# Arduino_CS.net
KiCad netlist of a schematic drawn in EAGLE
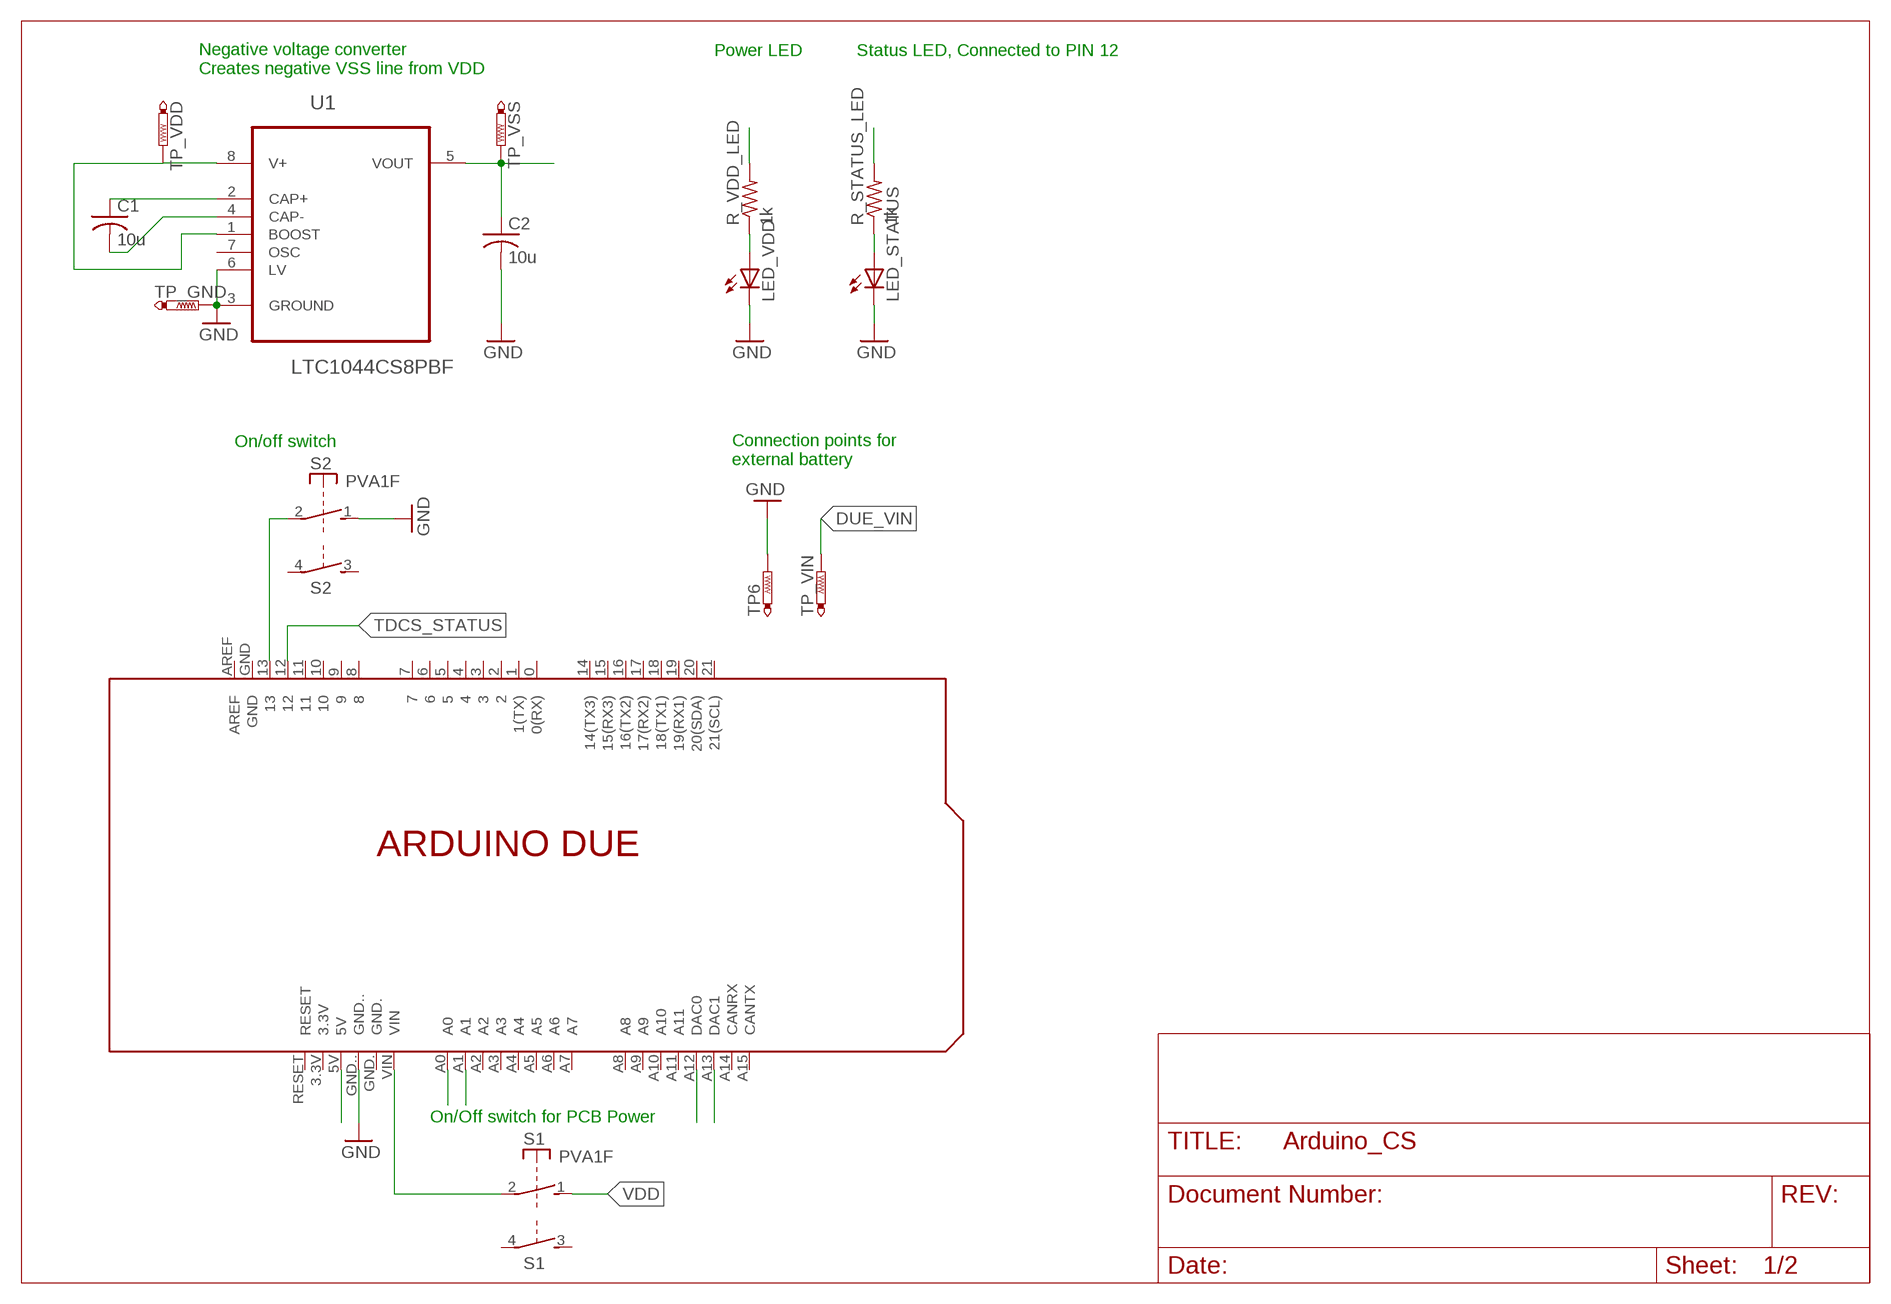
[diagram p0: schematic, sheet 1]
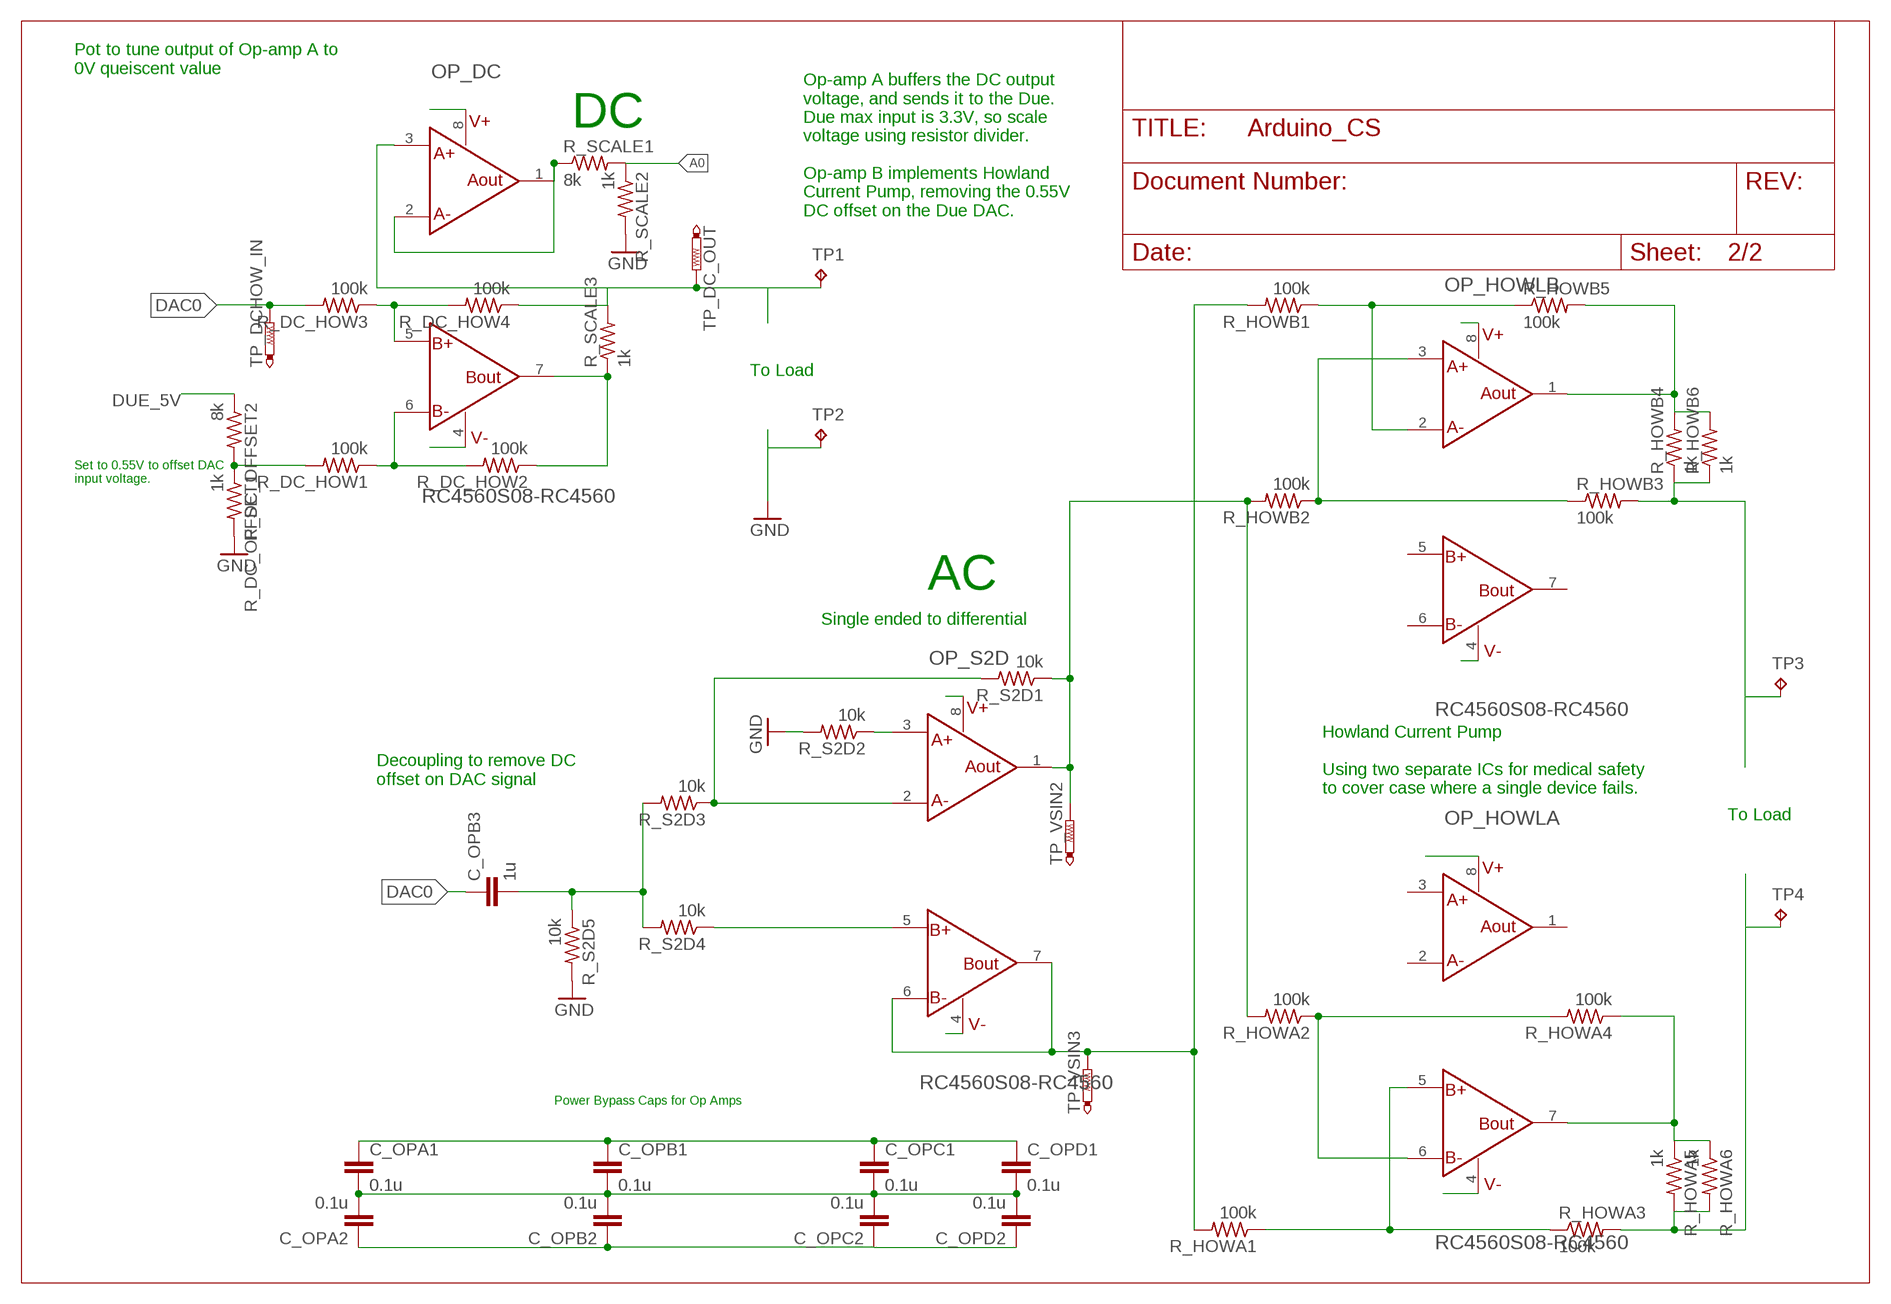
[diagram p1: schematic, sheet 2]

(export (version "E")
  (design (tool "Eeschema 10.0.6"))
  (components
    (comp (ref "C_OPA1")
      (value "0.1u")
      (footprint "eagle-import:C0805")
      (libsource (lib "eagle-import") (part "C-EUC0805"))
    )
    (comp (ref "C_OPA2")
      (value "0.1u")
      (footprint "eagle-import:C0805")
      (libsource (lib "eagle-import") (part "C-EUC0805"))
    )
    (comp (ref "C_OPB1")
      (value "0.1u")
      (footprint "eagle-import:C0805")
      (libsource (lib "eagle-import") (part "C-EUC0805"))
    )
    (comp (ref "C_OPB2")
      (value "0.1u")
      (footprint "eagle-import:C0805")
      (libsource (lib "eagle-import") (part "C-EUC0805"))
    )
    (comp (ref "C_OPB3")
      (value "1u")
      (footprint "eagle-import:C0805")
      (libsource (lib "eagle-import") (part "C-EUC0805"))
    )
    (comp (ref "C_OPC1")
      (value "0.1u")
      (footprint "eagle-import:C0805")
      (libsource (lib "eagle-import") (part "C-EUC0805"))
    )
    (comp (ref "C_OPC2")
      (value "0.1u")
      (footprint "eagle-import:C0805")
      (libsource (lib "eagle-import") (part "C-EUC0805"))
    )
    (comp (ref "C_OPD1")
      (value "0.1u")
      (footprint "eagle-import:C0805")
      (libsource (lib "eagle-import") (part "C-EUC0805"))
    )
    (comp (ref "C_OPD2")
      (value "0.1u")
      (footprint "eagle-import:C0805")
      (libsource (lib "eagle-import") (part "C-EUC0805"))
    )
    (comp (ref "OP_DC")
      (value "RC4560S08-RC4560")
      (footprint "eagle-import:SO8")
      (libsource (lib "eagle-import") (part "RC4560S08-RC4560"))
    )
    (comp (ref "OP_HOWLA")
      (value "RC4560S08-RC4560")
      (footprint "eagle-import:SO8")
      (libsource (lib "eagle-import") (part "RC4560S08-RC4560"))
    )
    (comp (ref "OP_HOWLB")
      (value "RC4560S08-RC4560")
      (footprint "eagle-import:SO8")
      (libsource (lib "eagle-import") (part "RC4560S08-RC4560"))
    )
    (comp (ref "OP_S2D")
      (value "RC4560S08-RC4560")
      (footprint "eagle-import:SO8")
      (libsource (lib "eagle-import") (part "RC4560S08-RC4560"))
    )
    (comp (ref "R_DC_HOW1")
      (value "100k")
      (footprint "eagle-import:R0805")
      (libsource (lib "eagle-import") (part "R-US_R0805"))
    )
    (comp (ref "R_DC_HOW2")
      (value "100k")
      (footprint "eagle-import:R0805")
      (libsource (lib "eagle-import") (part "R-US_R0805"))
    )
    (comp (ref "R_DC_HOW3")
      (value "100k")
      (footprint "eagle-import:R0805")
      (libsource (lib "eagle-import") (part "R-US_R0805"))
    )
    (comp (ref "R_DC_HOW4")
      (value "100k")
      (footprint "eagle-import:R0805")
      (libsource (lib "eagle-import") (part "R-US_R0805"))
    )
    (comp (ref "R_DC_OFFSET1")
      (value "1k")
      (footprint "eagle-import:R0805")
      (libsource (lib "eagle-import") (part "R-US_R0805"))
    )
    (comp (ref "R_DC_OFFSET2")
      (value "8k")
      (footprint "eagle-import:R0805")
      (libsource (lib "eagle-import") (part "R-US_R0805"))
    )
    (comp (ref "R_HOWA1")
      (value "100k")
      (footprint "eagle-import:R0805")
      (libsource (lib "eagle-import") (part "R-US_R0805"))
    )
    (comp (ref "R_HOWA2")
      (value "100k")
      (footprint "eagle-import:R0805")
      (libsource (lib "eagle-import") (part "R-US_R0805"))
    )
    (comp (ref "R_HOWA3")
      (value "100k")
      (footprint "eagle-import:R0805")
      (libsource (lib "eagle-import") (part "R-US_R0805"))
    )
    (comp (ref "R_HOWA4")
      (value "100k")
      (footprint "eagle-import:R0805")
      (libsource (lib "eagle-import") (part "R-US_R0805"))
    )
    (comp (ref "R_HOWA5")
      (value "1k")
      (footprint "eagle-import:R0805")
      (libsource (lib "eagle-import") (part "R-US_R0805"))
    )
    (comp (ref "R_HOWA6")
      (value "1k")
      (footprint "eagle-import:R0805")
      (libsource (lib "eagle-import") (part "R-US_R0805"))
    )
    (comp (ref "R_HOWB1")
      (value "100k")
      (footprint "eagle-import:R0805")
      (libsource (lib "eagle-import") (part "R-US_R0805"))
    )
    (comp (ref "R_HOWB2")
      (value "100k")
      (footprint "eagle-import:R0805")
      (libsource (lib "eagle-import") (part "R-US_R0805"))
    )
    (comp (ref "R_HOWB3")
      (value "100k")
      (footprint "eagle-import:R0805")
      (libsource (lib "eagle-import") (part "R-US_R0805"))
    )
    (comp (ref "R_HOWB4")
      (value "1k")
      (footprint "eagle-import:R0805")
      (libsource (lib "eagle-import") (part "R-US_R0805"))
    )
    (comp (ref "R_HOWB5")
      (value "100k")
      (footprint "eagle-import:R0805")
      (libsource (lib "eagle-import") (part "R-US_R0805"))
    )
    (comp (ref "R_HOWB6")
      (value "1k")
      (footprint "eagle-import:R0805")
      (libsource (lib "eagle-import") (part "R-US_R0805"))
    )
    (comp (ref "R_S2D1")
      (value "10k")
      (footprint "eagle-import:R0805")
      (libsource (lib "eagle-import") (part "R-US_R0805"))
    )
    (comp (ref "R_S2D2")
      (value "10k")
      (footprint "eagle-import:R0805")
      (libsource (lib "eagle-import") (part "R-US_R0805"))
    )
    (comp (ref "R_S2D3")
      (value "10k")
      (footprint "eagle-import:R0805")
      (libsource (lib "eagle-import") (part "R-US_R0805"))
    )
    (comp (ref "R_S2D4")
      (value "10k")
      (footprint "eagle-import:R0805")
      (libsource (lib "eagle-import") (part "R-US_R0805"))
    )
    (comp (ref "R_S2D5")
      (value "10k")
      (footprint "eagle-import:R0805")
      (libsource (lib "eagle-import") (part "R-US_R0805"))
    )
    (comp (ref "R_SCALE1")
      (value "8k")
      (footprint "eagle-import:R0805")
      (libsource (lib "eagle-import") (part "R-US_R0805"))
    )
    (comp (ref "R_SCALE2")
      (value "1k")
      (footprint "eagle-import:R0805")
      (libsource (lib "eagle-import") (part "R-US_R0805"))
    )
    (comp (ref "R_SCALE3")
      (value "1k")
      (footprint "eagle-import:R0805")
      (libsource (lib "eagle-import") (part "R-US_R0805"))
    )
    (comp (ref "TP1")
      (value "TPPAD1-20")
      (footprint "eagle-import:P1-20")
      (libsource (lib "eagle-import") (part "TPPAD1-20"))
    )
    (comp (ref "TP2")
      (value "TPPAD1-20")
      (footprint "eagle-import:P1-20")
      (libsource (lib "eagle-import") (part "TPPAD1-20"))
    )
    (comp (ref "TP3")
      (value "TPPAD1-20")
      (footprint "eagle-import:P1-20")
      (libsource (lib "eagle-import") (part "TPPAD1-20"))
    )
    (comp (ref "TP4")
      (value "TPPAD1-20")
      (footprint "eagle-import:P1-20")
      (libsource (lib "eagle-import") (part "TPPAD1-20"))
    )
    (comp (ref "TP_DCHOW_IN")
      (value "PTR1PAD1-13")
      (footprint "eagle-import:P1-13")
      (libsource (lib "eagle-import") (part "PTR1PAD1-13"))
    )
    (comp (ref "TP_DC_OUT")
      (value "PTR1PAD1-13")
      (footprint "eagle-import:P1-13")
      (libsource (lib "eagle-import") (part "PTR1PAD1-13"))
    )
    (comp (ref "TP_VSIN2")
      (value "PTR1PAD1-13")
      (footprint "eagle-import:P1-13")
      (libsource (lib "eagle-import") (part "PTR1PAD1-13"))
    )
    (comp (ref "TP_VSIN3")
      (value "PTR1PAD1-13")
      (footprint "eagle-import:P1-13")
      (libsource (lib "eagle-import") (part "PTR1PAD1-13"))
    )
    (comp (ref "C1")
      (value "10u")
      (footprint "eagle-import:C0805")
      (libsource (lib "eagle-import") (part "C-USC0805"))
    )
    (comp (ref "C2")
      (value "10u")
      (footprint "eagle-import:C0805")
      (libsource (lib "eagle-import") (part "C-USC0805"))
    )
    (comp (ref "LED_STATUS")
      (value "LEDSML0805")
      (footprint "eagle-import:SML0805")
      (libsource (lib "eagle-import") (part "LEDSML0805"))
    )
    (comp (ref "LED_VDD")
      (value "LEDSML0805")
      (footprint "eagle-import:SML0805")
      (libsource (lib "eagle-import") (part "LEDSML0805"))
    )
    (comp (ref "PCB1")
      (value "ARDUINO_DUE")
      (footprint "eagle-import:ARDUINO_DUE")
      (libsource (lib "eagle-import") (part "ARDUINO_DUE"))
    )
    (comp (ref "R_STATUS_LED")
      (value "1k")
      (footprint "eagle-import:M0805")
      (libsource (lib "eagle-import") (part "resistor_R-US_M0805"))
    )
    (comp (ref "R_VDD_LED")
      (value "1k")
      (footprint "eagle-import:M0805")
      (libsource (lib "eagle-import") (part "resistor_R-US_M0805"))
    )
    (comp (ref "S1")
      (value "PVA1F")
      (footprint "eagle-import:PVA1F")
      (libsource (lib "eagle-import") (part "PVA1F"))
    )
    (comp (ref "S2")
      (value "PVA1F")
      (footprint "eagle-import:PVA1F")
      (libsource (lib "eagle-import") (part "PVA1F"))
    )
    (comp (ref "TP6")
      (value "PTR1PAD1-13")
      (footprint "eagle-import:P1-13")
      (libsource (lib "eagle-import") (part "PTR1PAD1-13"))
    )
    (comp (ref "TP_GND")
      (value "PTR1PAD1-13")
      (footprint "eagle-import:P1-13")
      (libsource (lib "eagle-import") (part "PTR1PAD1-13"))
    )
    (comp (ref "TP_VDD")
      (value "PTR1PAD1-13")
      (footprint "eagle-import:P1-13")
      (libsource (lib "eagle-import") (part "PTR1PAD1-13"))
    )
    (comp (ref "TP_VIN")
      (value "PTR1PAD1-13")
      (footprint "eagle-import:P1-13")
      (libsource (lib "eagle-import") (part "PTR1PAD1-13"))
    )
    (comp (ref "TP_VSS")
      (value "PTR1PAD1-13")
      (footprint "eagle-import:P1-13")
      (libsource (lib "eagle-import") (part "PTR1PAD1-13"))
    )
    (comp (ref "U1")
      (value "LTC1044CS8PBF")
      (footprint "eagle-import:SOIC127P600X175-8N")
      (fields (field (name "MPN") "LTC1044CS8#PBF"))
      (libsource (lib "eagle-import") (part "LTC1044CS8PBF"))
    )
  )
  (nets
    (net (code "1") (name "A0") (class "Default")
      (node (ref "PCB1") (pin "A0") (pinfunction "A0_A0") (pintype "bidirectional"))
      (node (ref "R_SCALE1") (pin "2") (pinfunction "2_2") (pintype "passive"))
      (node (ref "R_SCALE2") (pin "1") (pinfunction "1_1") (pintype "passive"))
    )
    (net (code "2") (name "DAC0") (class "Default")
      (node (ref "C_OPB3") (pin "1") (pinfunction "1_1") (pintype "passive"))
      (node (ref "PCB1") (pin "A12") (pinfunction "DAC0_A12") (pintype "bidirectional"))
      (node (ref "R_DC_HOW3") (pin "2") (pinfunction "2_2") (pintype "passive"))
      (node (ref "TP_DCHOW_IN") (pin "TP") (pinfunction "TP_TP") (pintype "input"))
    )
    (net (code "3") (name "DUE_5V") (class "Default")
      (node (ref "PCB1") (pin "5V") (pinfunction "5V_5V") (pintype "bidirectional"))
      (node (ref "R_DC_OFFSET2") (pin "1") (pinfunction "1_1") (pintype "passive"))
    )
    (net (code "4") (name "DUE_VIN") (class "Default")
      (node (ref "PCB1") (pin "VIN") (pinfunction "VIN_VIN") (pintype "bidirectional"))
      (node (ref "S1") (pin "2") (pinfunction "P_2") (pintype "passive"))
      (node (ref "TP_VIN") (pin "TP") (pinfunction "TP_TP") (pintype "input"))
    )
    (net (code "5") (name "GND") (class "Default")
      (node (ref "C2") (pin "2") (pinfunction "2_2") (pintype "passive"))
      (node (ref "C_OPA1") (pin "2") (pinfunction "2_2") (pintype "passive"))
      (node (ref "C_OPA2") (pin "2") (pinfunction "2_2") (pintype "passive"))
      (node (ref "C_OPB1") (pin "2") (pinfunction "2_2") (pintype "passive"))
      (node (ref "C_OPB2") (pin "2") (pinfunction "2_2") (pintype "passive"))
      (node (ref "C_OPC1") (pin "2") (pinfunction "2_2") (pintype "passive"))
      (node (ref "C_OPC2") (pin "2") (pinfunction "2_2") (pintype "passive"))
      (node (ref "C_OPD1") (pin "2") (pinfunction "2_2") (pintype "passive"))
      (node (ref "C_OPD2") (pin "2") (pinfunction "2_2") (pintype "passive"))
      (node (ref "LED_STATUS") (pin "C") (pinfunction "C_C") (pintype "passive"))
      (node (ref "LED_VDD") (pin "C") (pinfunction "C_C") (pintype "passive"))
      (node (ref "PCB1") (pin "GND..") (pinfunction "GND.._GND..") (pintype "bidirectional"))
      (node (ref "R_DC_OFFSET1") (pin "2") (pinfunction "2_2") (pintype "passive"))
      (node (ref "R_S2D2") (pin "2") (pinfunction "2_2") (pintype "passive"))
      (node (ref "R_S2D5") (pin "2") (pinfunction "2_2") (pintype "passive"))
      (node (ref "R_SCALE2") (pin "2") (pinfunction "2_2") (pintype "passive"))
      (node (ref "S2") (pin "1") (pinfunction "S_1") (pintype "passive"))
      (node (ref "TP2") (pin "TP") (pinfunction "TP_TP") (pintype "input"))
      (node (ref "TP6") (pin "TP") (pinfunction "TP_TP") (pintype "input"))
      (node (ref "TP_GND") (pin "TP") (pinfunction "TP_TP") (pintype "input"))
      (node (ref "U1") (pin "3") (pinfunction "GROUND_3") (pintype "passive"))
      (node (ref "U1") (pin "6") (pinfunction "LV_6") (pintype "input"))
    )
    (net (code "6") (name "Net-(C_OPB3-Pad2)") (class "Default")
      (node (ref "C_OPB3") (pin "2") (pinfunction "2_2") (pintype "passive"))
      (node (ref "R_S2D3") (pin "2") (pinfunction "2_2") (pintype "passive"))
      (node (ref "R_S2D4") (pin "2") (pinfunction "2_2") (pintype "passive"))
      (node (ref "R_S2D5") (pin "1") (pinfunction "1_1") (pintype "passive"))
    )
    (net (code "7") (name "Net-(LED_STATUS-PadA)") (class "Default")
      (node (ref "LED_STATUS") (pin "A") (pinfunction "A_A") (pintype "passive"))
      (node (ref "R_STATUS_LED") (pin "1") (pinfunction "1_1") (pintype "passive"))
    )
    (net (code "8") (name "Net-(LED_VDD-PadA)") (class "Default")
      (node (ref "LED_VDD") (pin "A") (pinfunction "A_A") (pintype "passive"))
      (node (ref "R_VDD_LED") (pin "1") (pinfunction "1_1") (pintype "passive"))
    )
    (net (code "9") (name "Net-(OP_DC-NEGA)") (class "Default")
      (node (ref "OP_DC") (pin "1") (pinfunction "OUTA_1") (pintype "output"))
      (node (ref "OP_DC") (pin "2") (pinfunction "NEGA_2") (pintype "input"))
      (node (ref "R_SCALE1") (pin "1") (pinfunction "1_1") (pintype "passive"))
    )
    (net (code "10") (name "Net-(OP_DC-NEGB)") (class "Default")
      (node (ref "OP_DC") (pin "6") (pinfunction "NEGB_6") (pintype "input"))
      (node (ref "R_DC_HOW1") (pin "1") (pinfunction "1_1") (pintype "passive"))
      (node (ref "R_DC_HOW2") (pin "2") (pinfunction "2_2") (pintype "passive"))
    )
    (net (code "11") (name "Net-(OP_DC-OUTB)") (class "Default")
      (node (ref "OP_DC") (pin "7") (pinfunction "OUTB_7") (pintype "output"))
      (node (ref "R_DC_HOW2") (pin "1") (pinfunction "1_1") (pintype "passive"))
      (node (ref "R_SCALE3") (pin "1") (pinfunction "1_1") (pintype "passive"))
    )
    (net (code "12") (name "Net-(OP_DC-POSA)") (class "Default")
      (node (ref "OP_DC") (pin "3") (pinfunction "POSA_3") (pintype "input"))
      (node (ref "R_DC_HOW4") (pin "1") (pinfunction "1_1") (pintype "passive"))
      (node (ref "R_SCALE3") (pin "2") (pinfunction "2_2") (pintype "passive"))
      (node (ref "TP1") (pin "TP") (pinfunction "TP_TP") (pintype "input"))
      (node (ref "TP_DC_OUT") (pin "TP") (pinfunction "TP_TP") (pintype "input"))
    )
    (net (code "13") (name "Net-(OP_DC-POSB)") (class "Default")
      (node (ref "OP_DC") (pin "5") (pinfunction "POSB_5") (pintype "input"))
      (node (ref "R_DC_HOW3") (pin "1") (pinfunction "1_1") (pintype "passive"))
      (node (ref "R_DC_HOW4") (pin "2") (pinfunction "2_2") (pintype "passive"))
    )
    (net (code "14") (name "Net-(OP_HOWLA-NEGB)") (class "Default")
      (node (ref "OP_HOWLA") (pin "6") (pinfunction "NEGB_6") (pintype "input"))
      (node (ref "R_HOWA2") (pin "1") (pinfunction "1_1") (pintype "passive"))
      (node (ref "R_HOWA4") (pin "2") (pinfunction "2_2") (pintype "passive"))
    )
    (net (code "15") (name "Net-(OP_HOWLA-OUTB)") (class "Default")
      (node (ref "OP_HOWLA") (pin "7") (pinfunction "OUTB_7") (pintype "output"))
      (node (ref "R_HOWA4") (pin "1") (pinfunction "1_1") (pintype "passive"))
      (node (ref "R_HOWA5") (pin "1") (pinfunction "1_1") (pintype "passive"))
      (node (ref "R_HOWA6") (pin "1") (pinfunction "1_1") (pintype "passive"))
    )
    (net (code "16") (name "Net-(OP_HOWLA-POSB)") (class "Default")
      (node (ref "OP_HOWLA") (pin "5") (pinfunction "POSB_5") (pintype "input"))
      (node (ref "R_HOWA1") (pin "1") (pinfunction "1_1") (pintype "passive"))
      (node (ref "R_HOWA3") (pin "1") (pinfunction "1_1") (pintype "passive"))
    )
    (net (code "17") (name "Net-(OP_HOWLB-NEGA)") (class "Default")
      (node (ref "OP_HOWLB") (pin "2") (pinfunction "NEGA_2") (pintype "input"))
      (node (ref "R_HOWB1") (pin "1") (pinfunction "1_1") (pintype "passive"))
      (node (ref "R_HOWB5") (pin "1") (pinfunction "1_1") (pintype "passive"))
    )
    (net (code "18") (name "Net-(OP_HOWLB-OUTA)") (class "Default")
      (node (ref "OP_HOWLB") (pin "1") (pinfunction "OUTA_1") (pintype "output"))
      (node (ref "R_HOWB4") (pin "2") (pinfunction "2_2") (pintype "passive"))
      (node (ref "R_HOWB5") (pin "2") (pinfunction "2_2") (pintype "passive"))
      (node (ref "R_HOWB6") (pin "2") (pinfunction "2_2") (pintype "passive"))
    )
    (net (code "19") (name "Net-(OP_HOWLB-POSA)") (class "Default")
      (node (ref "OP_HOWLB") (pin "3") (pinfunction "POSA_3") (pintype "input"))
      (node (ref "R_HOWB2") (pin "1") (pinfunction "1_1") (pintype "passive"))
      (node (ref "R_HOWB3") (pin "1") (pinfunction "1_1") (pintype "passive"))
    )
    (net (code "20") (name "Net-(OP_S2D-NEGA)") (class "Default")
      (node (ref "OP_S2D") (pin "2") (pinfunction "NEGA_2") (pintype "input"))
      (node (ref "R_S2D1") (pin "2") (pinfunction "2_2") (pintype "passive"))
      (node (ref "R_S2D3") (pin "1") (pinfunction "1_1") (pintype "passive"))
    )
    (net (code "21") (name "Net-(OP_S2D-NEGB)") (class "Default")
      (node (ref "OP_S2D") (pin "6") (pinfunction "NEGB_6") (pintype "input"))
      (node (ref "OP_S2D") (pin "7") (pinfunction "OUTB_7") (pintype "output"))
      (node (ref "R_HOWA1") (pin "2") (pinfunction "2_2") (pintype "passive"))
      (node (ref "R_HOWB1") (pin "2") (pinfunction "2_2") (pintype "passive"))
      (node (ref "TP_VSIN3") (pin "TP") (pinfunction "TP_TP") (pintype "input"))
    )
    (net (code "22") (name "Net-(OP_S2D-OUTA)") (class "Default")
      (node (ref "OP_S2D") (pin "1") (pinfunction "OUTA_1") (pintype "output"))
      (node (ref "R_HOWA2") (pin "2") (pinfunction "2_2") (pintype "passive"))
      (node (ref "R_HOWB2") (pin "2") (pinfunction "2_2") (pintype "passive"))
      (node (ref "R_S2D1") (pin "1") (pinfunction "1_1") (pintype "passive"))
      (node (ref "TP_VSIN2") (pin "TP") (pinfunction "TP_TP") (pintype "input"))
    )
    (net (code "23") (name "Net-(OP_S2D-POSA)") (class "Default")
      (node (ref "OP_S2D") (pin "3") (pinfunction "POSA_3") (pintype "input"))
      (node (ref "R_S2D2") (pin "1") (pinfunction "1_1") (pintype "passive"))
    )
    (net (code "24") (name "Net-(OP_S2D-POSB)") (class "Default")
      (node (ref "OP_S2D") (pin "5") (pinfunction "POSB_5") (pintype "input"))
      (node (ref "R_S2D4") (pin "1") (pinfunction "1_1") (pintype "passive"))
    )
    (net (code "25") (name "Net-(R_DC_HOW1-Pad2)") (class "Default")
      (node (ref "R_DC_HOW1") (pin "2") (pinfunction "2_2") (pintype "passive"))
      (node (ref "R_DC_OFFSET1") (pin "1") (pinfunction "1_1") (pintype "passive"))
      (node (ref "R_DC_OFFSET2") (pin "2") (pinfunction "2_2") (pintype "passive"))
    )
    (net (code "26") (name "Net-(R_HOWA3-Pad2)") (class "Default")
      (node (ref "R_HOWA3") (pin "2") (pinfunction "2_2") (pintype "passive"))
      (node (ref "R_HOWA5") (pin "2") (pinfunction "2_2") (pintype "passive"))
      (node (ref "R_HOWA6") (pin "2") (pinfunction "2_2") (pintype "passive"))
      (node (ref "TP4") (pin "TP") (pinfunction "TP_TP") (pintype "input"))
    )
    (net (code "27") (name "Net-(R_HOWB3-Pad2)") (class "Default")
      (node (ref "R_HOWB3") (pin "2") (pinfunction "2_2") (pintype "passive"))
      (node (ref "R_HOWB4") (pin "1") (pinfunction "1_1") (pintype "passive"))
      (node (ref "R_HOWB6") (pin "1") (pinfunction "1_1") (pintype "passive"))
      (node (ref "TP3") (pin "TP") (pinfunction "TP_TP") (pintype "input"))
    )
    (net (code "28") (name "Net-(S2A-P)") (class "Default")
      (node (ref "PCB1") (pin "13") (pinfunction "13_13") (pintype "bidirectional"))
      (node (ref "S2") (pin "2") (pinfunction "P_2") (pintype "passive"))
    )
    (net (code "29") (name "Net-(U1-CAP+)") (class "Default")
      (node (ref "C1") (pin "1") (pinfunction "1_1") (pintype "passive"))
      (node (ref "U1") (pin "2") (pinfunction "CAP+_2") (pintype "passive"))
    )
    (net (code "30") (name "Net-(U1-CAP-)") (class "Default")
      (node (ref "C1") (pin "2") (pinfunction "2_2") (pintype "passive"))
      (node (ref "U1") (pin "4") (pinfunction "CAP-_4") (pintype "passive"))
    )
    (net (code "31") (name "TDCS_STATUS") (class "Default")
      (node (ref "PCB1") (pin "12") (pinfunction "12_12") (pintype "bidirectional"))
      (node (ref "R_STATUS_LED") (pin "2") (pinfunction "2_2") (pintype "passive"))
    )
    (net (code "32") (name "VDD") (class "Default")
      (node (ref "C_OPA1") (pin "1") (pinfunction "1_1") (pintype "passive"))
      (node (ref "C_OPB1") (pin "1") (pinfunction "1_1") (pintype "passive"))
      (node (ref "C_OPC1") (pin "1") (pinfunction "1_1") (pintype "passive"))
      (node (ref "C_OPD1") (pin "1") (pinfunction "1_1") (pintype "passive"))
      (node (ref "OP_DC") (pin "8") (pinfunction "V+_8") (pintype "power_in"))
      (node (ref "OP_HOWLA") (pin "8") (pinfunction "V+_8") (pintype "power_in"))
      (node (ref "OP_HOWLB") (pin "8") (pinfunction "V+_8") (pintype "power_in"))
      (node (ref "OP_S2D") (pin "8") (pinfunction "V+_8") (pintype "power_in"))
      (node (ref "R_VDD_LED") (pin "2") (pinfunction "2_2") (pintype "passive"))
      (node (ref "S1") (pin "1") (pinfunction "S_1") (pintype "passive"))
      (node (ref "TP_VDD") (pin "TP") (pinfunction "TP_TP") (pintype "input"))
      (node (ref "U1") (pin "1") (pinfunction "BOOST_1") (pintype "input"))
      (node (ref "U1") (pin "8") (pinfunction "V+_8") (pintype "power_in"))
    )
    (net (code "33") (name "VSS") (class "Default")
      (node (ref "C2") (pin "1") (pinfunction "1_1") (pintype "passive"))
      (node (ref "C_OPA2") (pin "1") (pinfunction "1_1") (pintype "passive"))
      (node (ref "C_OPB2") (pin "1") (pinfunction "1_1") (pintype "passive"))
      (node (ref "C_OPC2") (pin "1") (pinfunction "1_1") (pintype "passive"))
      (node (ref "C_OPD2") (pin "1") (pinfunction "1_1") (pintype "passive"))
      (node (ref "OP_DC") (pin "4") (pinfunction "V-_4") (pintype "power_in"))
      (node (ref "OP_HOWLA") (pin "4") (pinfunction "V-_4") (pintype "power_in"))
      (node (ref "OP_HOWLB") (pin "4") (pinfunction "V-_4") (pintype "power_in"))
      (node (ref "OP_S2D") (pin "4") (pinfunction "V-_4") (pintype "power_in"))
      (node (ref "TP_VSS") (pin "TP") (pinfunction "TP_TP") (pintype "input"))
      (node (ref "U1") (pin "5") (pinfunction "VOUT_5") (pintype "output"))
    )
    (net (code "34") (name "unconnected-(OP_HOWLA-NEGA-Pad2)") (class "Default")
      (node (ref "OP_HOWLA") (pin "2") (pinfunction "NEGA_2") (pintype "input"))
    )
    (net (code "35") (name "unconnected-(OP_HOWLA-OUTA-Pad1)") (class "Default")
      (node (ref "OP_HOWLA") (pin "1") (pinfunction "OUTA_1") (pintype "output"))
    )
    (net (code "36") (name "unconnected-(OP_HOWLA-POSA-Pad3)") (class "Default")
      (node (ref "OP_HOWLA") (pin "3") (pinfunction "POSA_3") (pintype "input"))
    )
    (net (code "37") (name "unconnected-(OP_HOWLB-NEGB-Pad6)") (class "Default")
      (node (ref "OP_HOWLB") (pin "6") (pinfunction "NEGB_6") (pintype "input"))
    )
    (net (code "38") (name "unconnected-(OP_HOWLB-OUTB-Pad7)") (class "Default")
      (node (ref "OP_HOWLB") (pin "7") (pinfunction "OUTB_7") (pintype "output"))
    )
    (net (code "39") (name "unconnected-(OP_HOWLB-POSB-Pad5)") (class "Default")
      (node (ref "OP_HOWLB") (pin "5") (pinfunction "POSB_5") (pintype "input"))
    )
    (net (code "40") (name "unconnected-(PCB1-0(RX)-Pad0)") (class "Default")
      (node (ref "PCB1") (pin "0") (pinfunction "0(RX)_0") (pintype "bidirectional"))
    )
    (net (code "41") (name "unconnected-(PCB1-1(TX)-Pad1)") (class "Default")
      (node (ref "PCB1") (pin "1") (pinfunction "1(TX)_1") (pintype "bidirectional"))
    )
    (net (code "42") (name "unconnected-(PCB1-14(TX3)-Pad14)") (class "Default")
      (node (ref "PCB1") (pin "14") (pinfunction "14(TX3)_14") (pintype "bidirectional"))
    )
    (net (code "43") (name "unconnected-(PCB1-15(RX3)-Pad15)") (class "Default")
      (node (ref "PCB1") (pin "15") (pinfunction "15(RX3)_15") (pintype "bidirectional"))
    )
    (net (code "44") (name "unconnected-(PCB1-16(TX2)-Pad16)") (class "Default")
      (node (ref "PCB1") (pin "16") (pinfunction "16(TX2)_16") (pintype "bidirectional"))
    )
    (net (code "45") (name "unconnected-(PCB1-17(RX2)-Pad17)") (class "Default")
      (node (ref "PCB1") (pin "17") (pinfunction "17(RX2)_17") (pintype "bidirectional"))
    )
    (net (code "46") (name "unconnected-(PCB1-18(TX1)-Pad18)") (class "Default")
      (node (ref "PCB1") (pin "18") (pinfunction "18(TX1)_18") (pintype "bidirectional"))
    )
    (net (code "47") (name "unconnected-(PCB1-19(RX1)-Pad19)") (class "Default")
      (node (ref "PCB1") (pin "19") (pinfunction "19(RX1)_19") (pintype "bidirectional"))
    )
    (net (code "48") (name "unconnected-(PCB1-20(SDA)-Pad20)") (class "Default")
      (node (ref "PCB1") (pin "20") (pinfunction "20(SDA)_20") (pintype "bidirectional"))
    )
    (net (code "49") (name "unconnected-(PCB1-21(SCL)-Pad21)") (class "Default")
      (node (ref "PCB1") (pin "21") (pinfunction "21(SCL)_21") (pintype "bidirectional"))
    )
    (net (code "50") (name "unconnected-(PCB1-CANRX-PadA14)") (class "Default")
      (node (ref "PCB1") (pin "A14") (pinfunction "CANRX_A14") (pintype "bidirectional"))
    )
    (net (code "51") (name "unconnected-(PCB1-CANTX-PadA15)") (class "Default")
      (node (ref "PCB1") (pin "A15") (pinfunction "CANTX_A15") (pintype "bidirectional"))
    )
    (net (code "52") (name "unconnected-(PCB1-DAC1-PadA13)") (class "Default")
      (node (ref "PCB1") (pin "A13") (pinfunction "DAC1_A13") (pintype "bidirectional"))
    )
    (net (code "53") (name "unconnected-(PCB1-Pad2)") (class "Default")
      (node (ref "PCB1") (pin "2") (pinfunction "2_2") (pintype "bidirectional"))
    )
    (net (code "54") (name "unconnected-(PCB1-Pad3)") (class "Default")
      (node (ref "PCB1") (pin "3") (pinfunction "3_3") (pintype "bidirectional"))
    )
    (net (code "55") (name "unconnected-(PCB1-Pad3.3V)") (class "Default")
      (node (ref "PCB1") (pin "3.3V") (pinfunction "3.3V_3.3V") (pintype "bidirectional"))
    )
    (net (code "56") (name "unconnected-(PCB1-Pad4)") (class "Default")
      (node (ref "PCB1") (pin "4") (pinfunction "4_4") (pintype "bidirectional"))
    )
    (net (code "57") (name "unconnected-(PCB1-Pad5)") (class "Default")
      (node (ref "PCB1") (pin "5") (pinfunction "5_5") (pintype "bidirectional"))
    )
    (net (code "58") (name "unconnected-(PCB1-Pad6)") (class "Default")
      (node (ref "PCB1") (pin "6") (pinfunction "6_6") (pintype "bidirectional"))
    )
    (net (code "59") (name "unconnected-(PCB1-Pad7)") (class "Default")
      (node (ref "PCB1") (pin "7") (pinfunction "7_7") (pintype "bidirectional"))
    )
    (net (code "60") (name "unconnected-(PCB1-Pad8)") (class "Default")
      (node (ref "PCB1") (pin "8") (pinfunction "8_8") (pintype "bidirectional"))
    )
    (net (code "61") (name "unconnected-(PCB1-Pad9)") (class "Default")
      (node (ref "PCB1") (pin "9") (pinfunction "9_9") (pintype "bidirectional"))
    )
    (net (code "62") (name "unconnected-(PCB1-Pad10)") (class "Default")
      (node (ref "PCB1") (pin "10") (pinfunction "10_10") (pintype "bidirectional"))
    )
    (net (code "63") (name "unconnected-(PCB1-Pad11)") (class "Default")
      (node (ref "PCB1") (pin "11") (pinfunction "11_11") (pintype "bidirectional"))
    )
    (net (code "64") (name "unconnected-(PCB1-PadA1)") (class "Default")
      (node (ref "PCB1") (pin "A1") (pinfunction "A1_A1") (pintype "bidirectional"))
    )
    (net (code "65") (name "unconnected-(PCB1-PadA2)") (class "Default")
      (node (ref "PCB1") (pin "A2") (pinfunction "A2_A2") (pintype "bidirectional"))
    )
    (net (code "66") (name "unconnected-(PCB1-PadA3)") (class "Default")
      (node (ref "PCB1") (pin "A3") (pinfunction "A3_A3") (pintype "bidirectional"))
    )
    (net (code "67") (name "unconnected-(PCB1-PadA4)") (class "Default")
      (node (ref "PCB1") (pin "A4") (pinfunction "A4_A4") (pintype "bidirectional"))
    )
    (net (code "68") (name "unconnected-(PCB1-PadA5)") (class "Default")
      (node (ref "PCB1") (pin "A5") (pinfunction "A5_A5") (pintype "bidirectional"))
    )
    (net (code "69") (name "unconnected-(PCB1-PadA6)") (class "Default")
      (node (ref "PCB1") (pin "A6") (pinfunction "A6_A6") (pintype "bidirectional"))
    )
    (net (code "70") (name "unconnected-(PCB1-PadA7)") (class "Default")
      (node (ref "PCB1") (pin "A7") (pinfunction "A7_A7") (pintype "bidirectional"))
    )
    (net (code "71") (name "unconnected-(PCB1-PadA8)") (class "Default")
      (node (ref "PCB1") (pin "A8") (pinfunction "A8_A8") (pintype "bidirectional"))
    )
    (net (code "72") (name "unconnected-(PCB1-PadA9)") (class "Default")
      (node (ref "PCB1") (pin "A9") (pinfunction "A9_A9") (pintype "bidirectional"))
    )
    (net (code "73") (name "unconnected-(PCB1-PadA10)") (class "Default")
      (node (ref "PCB1") (pin "A10") (pinfunction "A10_A10") (pintype "bidirectional"))
    )
    (net (code "74") (name "unconnected-(PCB1-PadA11)") (class "Default")
      (node (ref "PCB1") (pin "A11") (pinfunction "A11_A11") (pintype "bidirectional"))
    )
    (net (code "75") (name "unconnected-(PCB1-PadAREF)") (class "Default")
      (node (ref "PCB1") (pin "AREF") (pinfunction "AREF_AREF") (pintype "bidirectional"))
    )
    (net (code "76") (name "unconnected-(PCB1-PadGND)") (class "Default")
      (node (ref "PCB1") (pin "GND") (pinfunction "GND_GND") (pintype "bidirectional"))
    )
    (net (code "77") (name "unconnected-(PCB1-PadGND.)") (class "Default")
      (node (ref "PCB1") (pin "GND.") (pinfunction "GND._GND.") (pintype "bidirectional"))
    )
    (net (code "78") (name "unconnected-(PCB1-PadRESET)") (class "Default")
      (node (ref "PCB1") (pin "RESET") (pinfunction "RESET_RESET") (pintype "bidirectional"))
    )
    (net (code "79") (name "unconnected-(S1B-P-Pad4)") (class "Default")
      (node (ref "S1") (pin "4") (pinfunction "P_4") (pintype "passive"))
    )
    (net (code "80") (name "unconnected-(S1B-S-Pad3)") (class "Default")
      (node (ref "S1") (pin "3") (pinfunction "S_3") (pintype "passive"))
    )
    (net (code "81") (name "unconnected-(S2B-P-Pad4)") (class "Default")
      (node (ref "S2") (pin "4") (pinfunction "P_4") (pintype "passive"))
    )
    (net (code "82") (name "unconnected-(S2B-S-Pad3)") (class "Default")
      (node (ref "S2") (pin "3") (pinfunction "S_3") (pintype "passive"))
    )
    (net (code "83") (name "unconnected-(U1-OSC-Pad7)") (class "Default")
      (node (ref "U1") (pin "7") (pinfunction "OSC_7") (pintype "input"))
    )
  )
)
